# model.net
KiCad netlist of a schematic drawn in EAGLE
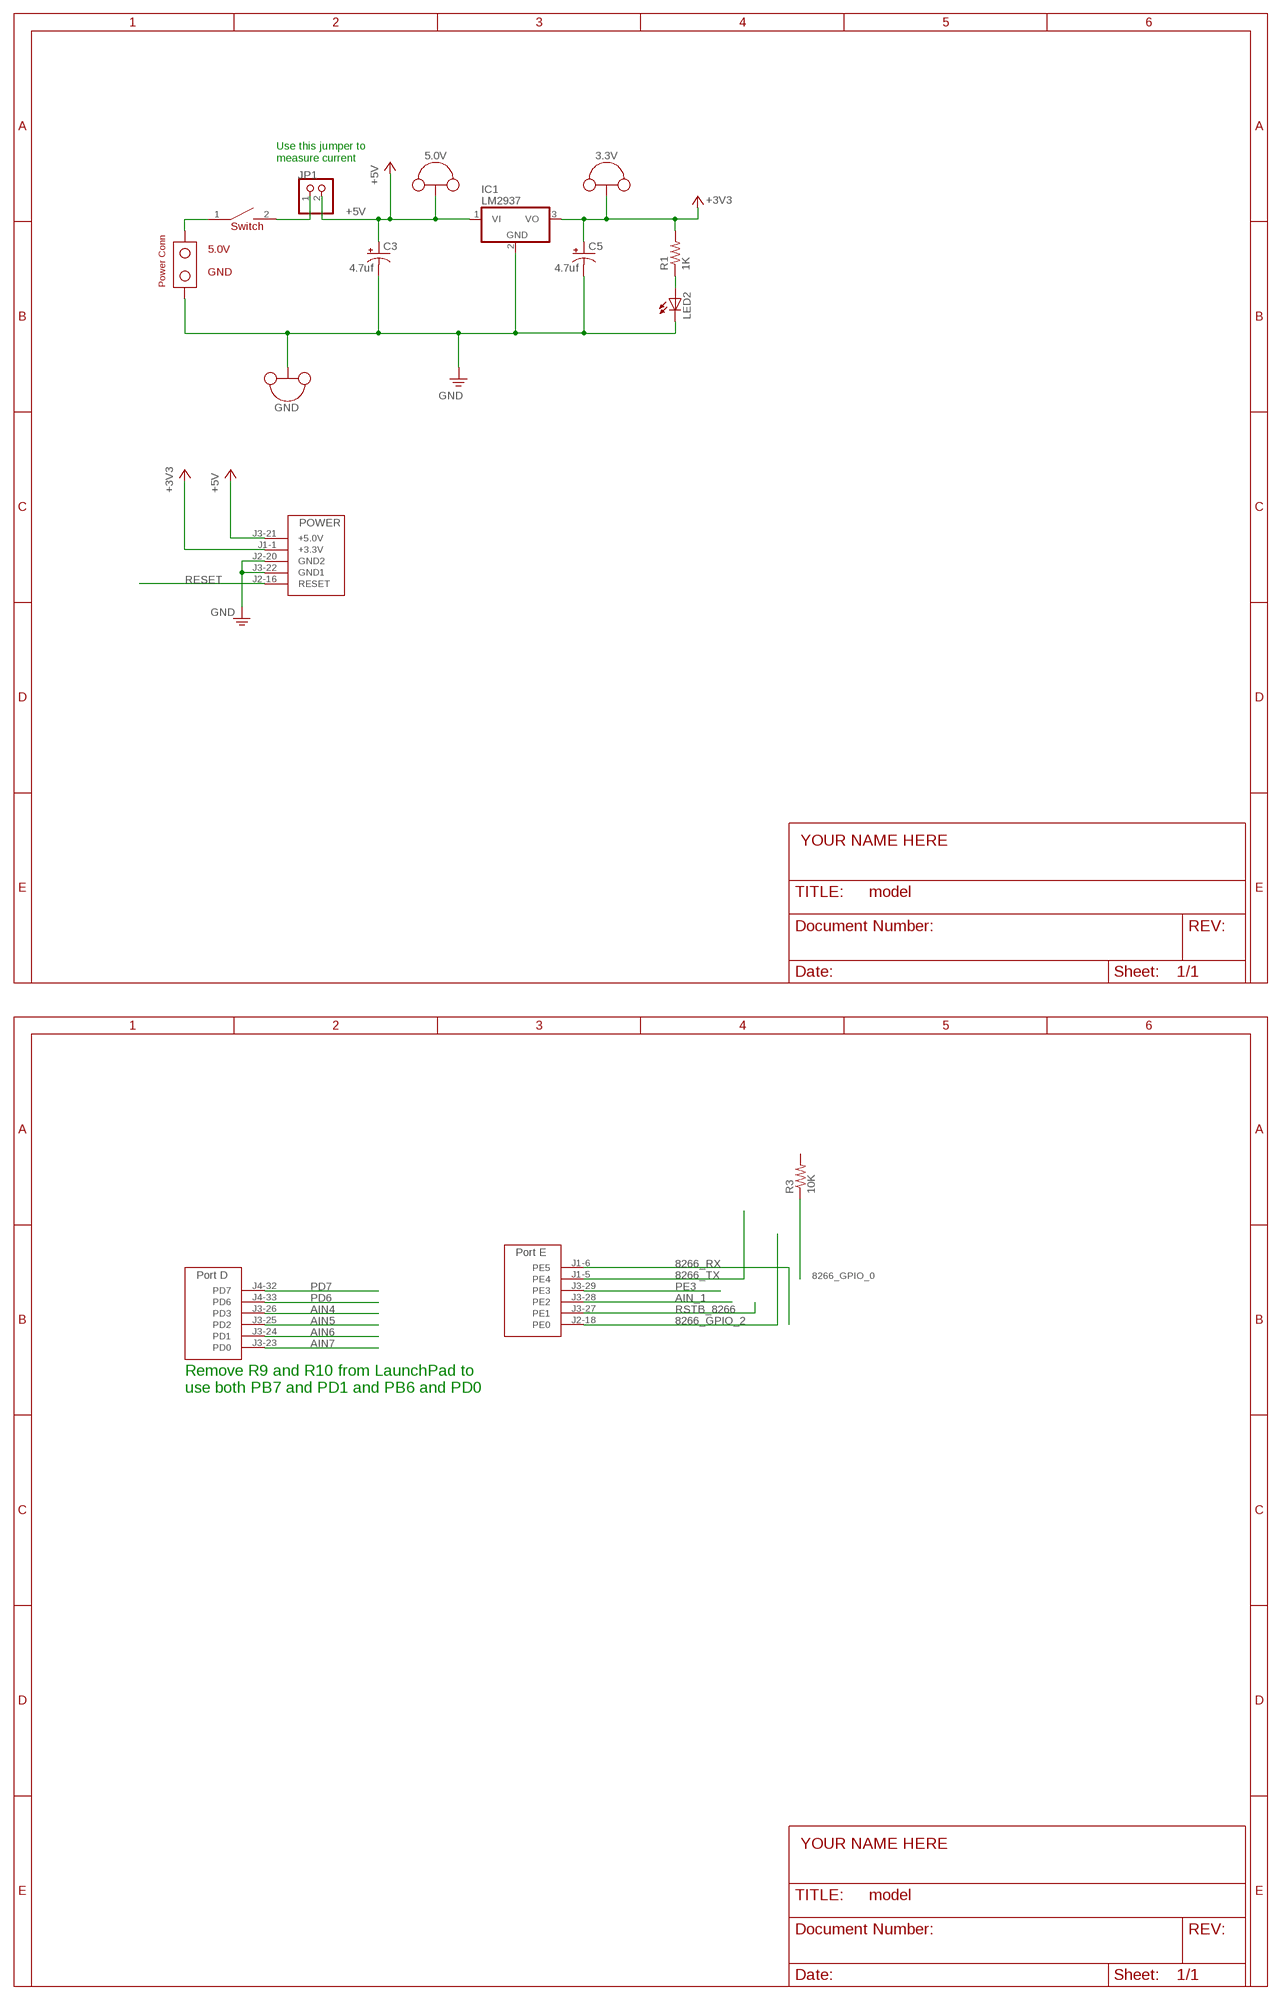
[diagram p0: schematic, sheet 1, part 1 of 2]
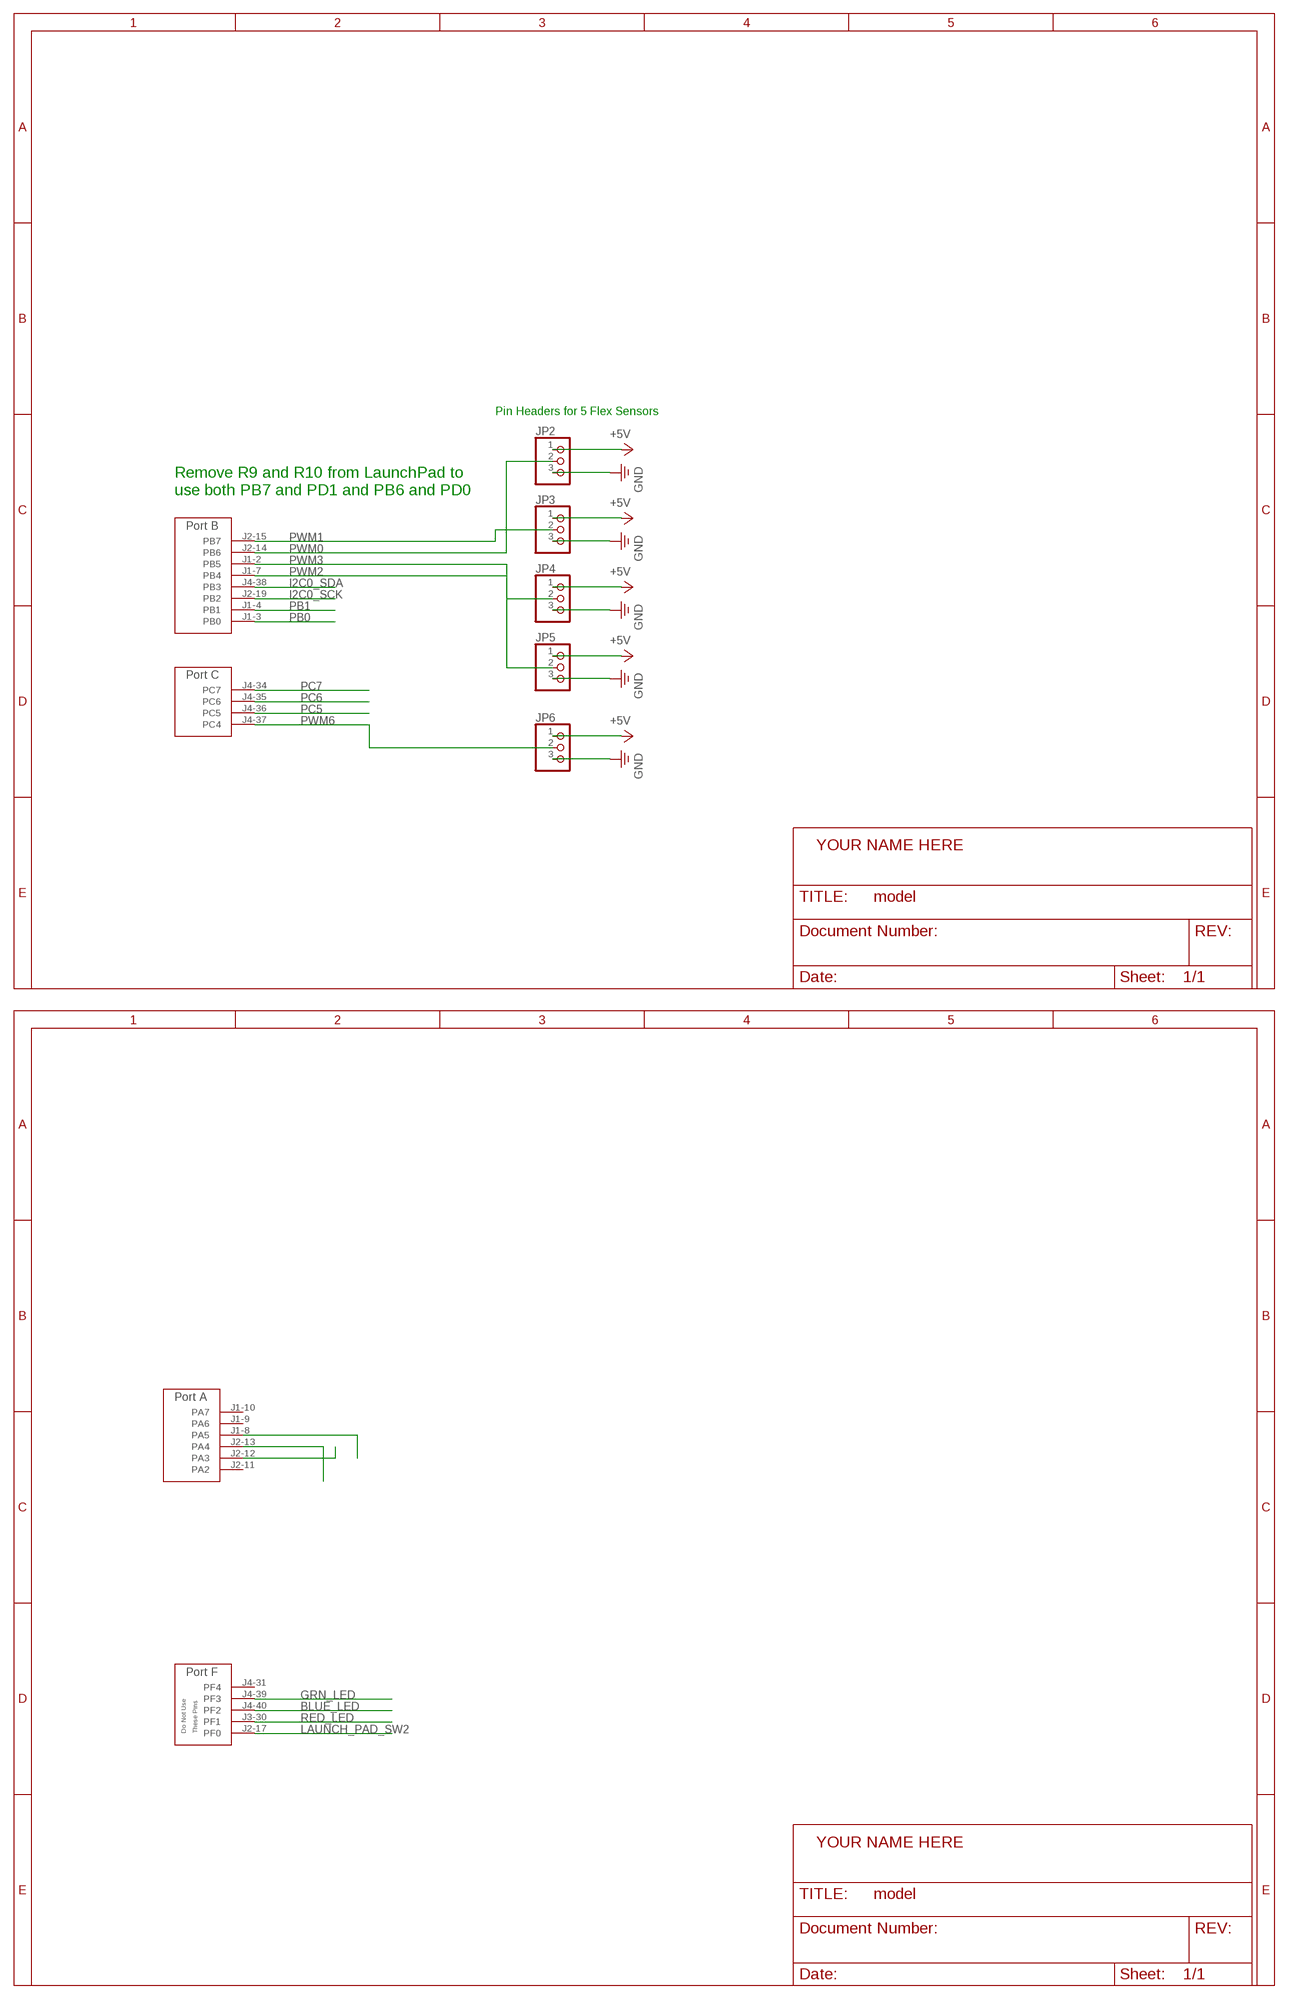
[diagram p1: schematic, sheet 1, part 2 of 2]

(export (version "E")
  (design (tool "Eeschema 10.0.6"))
  (components
    (comp (ref "3.3V")
      (value "TP_LOOP")
      (footprint "eagle-import:TP_LOOP")
      (libsource (lib "eagle-import") (part "TP_LOOP"))
    )
    (comp (ref "5.0V")
      (value "TP_LOOP")
      (footprint "eagle-import:TP_LOOP")
      (libsource (lib "eagle-import") (part "TP_LOOP"))
    )
    (comp (ref "C3")
      (value "4.7uf")
      (footprint "eagle-import:CAP200MILPOLARIZED")
      (libsource (lib "eagle-import") (part "CAPACITOR_POLARIZEDE5-6"))
    )
    (comp (ref "C5")
      (value "4.7uf")
      (footprint "eagle-import:CAP200MILPOLARIZED")
      (libsource (lib "eagle-import") (part "CAPACITOR_POLARIZEDE5-6"))
    )
    (comp (ref "GND")
      (value "TP_LOOP")
      (footprint "eagle-import:TP_LOOP")
      (libsource (lib "eagle-import") (part "TP_LOOP"))
    )
    (comp (ref "IC1")
      (value "LM2937")
      (footprint "eagle-import:TO220")
      (libsource (lib "eagle-import") (part "LM2937"))
    )
    (comp (ref "JP1")
      (value "PINHD-1X2")
      (footprint "eagle-import:1X02")
      (libsource (lib "eagle-import") (part "PINHD-1X2"))
    )
    (comp (ref "JP2")
      (value "PINHD-1X3")
      (footprint "eagle-import:1X03")
      (libsource (lib "eagle-import") (part "PINHD-1X3"))
    )
    (comp (ref "JP3")
      (value "PINHD-1X3")
      (footprint "eagle-import:1X03")
      (libsource (lib "eagle-import") (part "PINHD-1X3"))
    )
    (comp (ref "JP4")
      (value "PINHD-1X3")
      (footprint "eagle-import:1X03")
      (libsource (lib "eagle-import") (part "PINHD-1X3"))
    )
    (comp (ref "JP5")
      (value "PINHD-1X3")
      (footprint "eagle-import:1X03")
      (libsource (lib "eagle-import") (part "PINHD-1X3"))
    )
    (comp (ref "JP6")
      (value "PINHD-1X3")
      (footprint "eagle-import:1X03")
      (libsource (lib "eagle-import") (part "PINHD-1X3"))
    )
    (comp (ref "LED2")
      (value "LED3MM")
      (footprint "eagle-import:LED3MM")
      (libsource (lib "eagle-import") (part "LED3MM"))
    )
    (comp (ref "R1")
      (value "1K")
      (footprint "eagle-import:RES200MIL")
      (libsource (lib "eagle-import") (part "RESISTOR0204/5"))
    )
    (comp (ref "R3")
      (value "10K")
      (footprint "eagle-import:RES300MIL")
      (libsource (lib "eagle-import") (part "RESISTOR0204/7"))
    )
    (comp (ref "U$2")
      (value "TM4C_BP")
      (footprint "eagle-import:TM4C_BOOSTER_PACK")
      (libsource (lib "eagle-import") (part "TM4C_BP"))
    )
    (comp (ref "U$5")
      (value "POWER_CONN")
      (footprint "eagle-import:POWER_CONN")
      (libsource (lib "eagle-import") (part "POWER_CONN"))
    )
    (comp (ref "U$6")
      (value "SW_POWER_100MIL")
      (footprint "eagle-import:SW_POWER")
      (libsource (lib "eagle-import") (part "SW_POWER_100MIL"))
    )
  )
  (nets
    (net (code "1") (name "+3V3") (class "Default")
      (node (ref "3.3V") (pin "P$1") (pinfunction "TP_P$1") (pintype "bidirectional"))
      (node (ref "3.3V") (pin "P$2") (pinfunction "TP_P$2") (pintype "bidirectional"))
      (node (ref "C5") (pin "+") (pinfunction "+_+") (pintype "passive"))
      (node (ref "IC1") (pin "3") (pinfunction "VO_3") (pintype "passive"))
      (node (ref "R1") (pin "2") (pinfunction "2_2") (pintype "passive"))
      (node (ref "U$2") (pin "J1-1") (pinfunction "+3.3V_J1-1") (pintype "bidirectional"))
    )
    (net (code "2") (name "+5V") (class "Default")
      (node (ref "5.0V") (pin "P$1") (pinfunction "TP_P$1") (pintype "bidirectional"))
      (node (ref "5.0V") (pin "P$2") (pinfunction "TP_P$2") (pintype "bidirectional"))
      (node (ref "C3") (pin "+") (pinfunction "+_+") (pintype "passive"))
      (node (ref "IC1") (pin "1") (pinfunction "VI_1") (pintype "input"))
      (node (ref "JP1") (pin "2") (pinfunction "2_2") (pintype "passive"))
      (node (ref "JP2") (pin "1") (pinfunction "1_1") (pintype "passive"))
      (node (ref "JP3") (pin "1") (pinfunction "1_1") (pintype "passive"))
      (node (ref "JP4") (pin "1") (pinfunction "1_1") (pintype "passive"))
      (node (ref "JP5") (pin "1") (pinfunction "1_1") (pintype "passive"))
      (node (ref "JP6") (pin "1") (pinfunction "1_1") (pintype "passive"))
      (node (ref "U$2") (pin "J3-21") (pinfunction "+5.0V_J3-21") (pintype "bidirectional"))
    )
    (net (code "3") (name "/8266_GPIO_0") (class "Default")
      (node (ref "R3") (pin "1") (pinfunction "1_1") (pintype "passive"))
    )
    (net (code "4") (name "/8266_GPIO_2") (class "Default")
      (node (ref "U$2") (pin "J2-18") (pinfunction "PE0_J2-18") (pintype "bidirectional"))
    )
    (net (code "5") (name "/8266_RX") (class "Default")
      (node (ref "U$2") (pin "J1-6") (pinfunction "PE5_J1-6") (pintype "bidirectional"))
    )
    (net (code "6") (name "/8266_TX") (class "Default")
      (node (ref "U$2") (pin "J1-5") (pinfunction "PE4_J1-5") (pintype "bidirectional"))
    )
    (net (code "7") (name "/AIN4") (class "Default")
      (node (ref "U$2") (pin "J3-26") (pinfunction "PD3_J3-26") (pintype "bidirectional"))
    )
    (net (code "8") (name "/AIN5") (class "Default")
      (node (ref "U$2") (pin "J3-25") (pinfunction "PD2_J3-25") (pintype "bidirectional"))
    )
    (net (code "9") (name "/AIN6") (class "Default")
      (node (ref "U$2") (pin "J3-24") (pinfunction "PD1_J3-24") (pintype "bidirectional"))
    )
    (net (code "10") (name "/AIN7") (class "Default")
      (node (ref "U$2") (pin "J3-23") (pinfunction "PD0_J3-23") (pintype "bidirectional"))
    )
    (net (code "11") (name "/AIN_1") (class "Default")
      (node (ref "U$2") (pin "J3-28") (pinfunction "PE2_J3-28") (pintype "bidirectional"))
    )
    (net (code "12") (name "/BLUE_LED") (class "Default")
      (node (ref "U$2") (pin "J4-40") (pinfunction "PF2_J4-40") (pintype "bidirectional"))
    )
    (net (code "13") (name "/GRN_LED") (class "Default")
      (node (ref "U$2") (pin "J4-39") (pinfunction "PF3_J4-39") (pintype "bidirectional"))
    )
    (net (code "14") (name "/I2C0_SCK") (class "Default")
      (node (ref "U$2") (pin "J2-19") (pinfunction "PB2_J2-19") (pintype "bidirectional"))
    )
    (net (code "15") (name "/I2C0_SDA") (class "Default")
      (node (ref "U$2") (pin "J4-38") (pinfunction "PB3_J4-38") (pintype "bidirectional"))
    )
    (net (code "16") (name "/LAUNCH_PAD_SW2") (class "Default")
      (node (ref "U$2") (pin "J2-17") (pinfunction "PF0_J2-17") (pintype "bidirectional"))
    )
    (net (code "17") (name "/PB0") (class "Default")
      (node (ref "U$2") (pin "J1-3") (pinfunction "PB0_J1-3") (pintype "bidirectional"))
    )
    (net (code "18") (name "/PB1") (class "Default")
      (node (ref "U$2") (pin "J1-4") (pinfunction "PB1_J1-4") (pintype "bidirectional"))
    )
    (net (code "19") (name "/PC5") (class "Default")
      (node (ref "U$2") (pin "J4-36") (pinfunction "PC5_J4-36") (pintype "bidirectional"))
    )
    (net (code "20") (name "/PC6") (class "Default")
      (node (ref "U$2") (pin "J4-35") (pinfunction "PC6_J4-35") (pintype "bidirectional"))
    )
    (net (code "21") (name "/PC7") (class "Default")
      (node (ref "U$2") (pin "J4-34") (pinfunction "PC7_J4-34") (pintype "bidirectional"))
    )
    (net (code "22") (name "/PD6") (class "Default")
      (node (ref "U$2") (pin "J4-33") (pinfunction "PD6_J4-33") (pintype "bidirectional"))
    )
    (net (code "23") (name "/PD7") (class "Default")
      (node (ref "U$2") (pin "J4-32") (pinfunction "PD7_J4-32") (pintype "bidirectional"))
    )
    (net (code "24") (name "/PE3") (class "Default")
      (node (ref "U$2") (pin "J3-29") (pinfunction "PE3_J3-29") (pintype "bidirectional"))
    )
    (net (code "25") (name "/PWM0") (class "Default")
      (node (ref "JP2") (pin "2") (pinfunction "2_2") (pintype "passive"))
      (node (ref "U$2") (pin "J2-14") (pinfunction "PB6_J2-14") (pintype "bidirectional"))
    )
    (net (code "26") (name "/PWM1") (class "Default")
      (node (ref "JP3") (pin "2") (pinfunction "2_2") (pintype "passive"))
      (node (ref "U$2") (pin "J2-15") (pinfunction "PB7_J2-15") (pintype "bidirectional"))
    )
    (net (code "27") (name "/PWM2") (class "Default")
      (node (ref "JP4") (pin "2") (pinfunction "2_2") (pintype "passive"))
      (node (ref "U$2") (pin "J1-7") (pinfunction "PB4_J1-7") (pintype "bidirectional"))
    )
    (net (code "28") (name "/PWM3") (class "Default")
      (node (ref "JP5") (pin "2") (pinfunction "2_2") (pintype "passive"))
      (node (ref "U$2") (pin "J1-2") (pinfunction "PB5_J1-2") (pintype "bidirectional"))
    )
    (net (code "29") (name "/PWM6") (class "Default")
      (node (ref "JP6") (pin "2") (pinfunction "2_2") (pintype "passive"))
      (node (ref "U$2") (pin "J4-37") (pinfunction "PC4_J4-37") (pintype "bidirectional"))
    )
    (net (code "30") (name "/RED_LED") (class "Default")
      (node (ref "U$2") (pin "J3-30") (pinfunction "PF1_J3-30") (pintype "bidirectional"))
    )
    (net (code "31") (name "/RESET") (class "Default")
      (node (ref "U$2") (pin "J2-16") (pinfunction "RESET_J2-16") (pintype "bidirectional"))
    )
    (net (code "32") (name "/RSTB_8266") (class "Default")
      (node (ref "U$2") (pin "J3-27") (pinfunction "PE1_J3-27") (pintype "bidirectional"))
    )
    (net (code "33") (name "GND") (class "Default")
      (node (ref "C3") (pin "-") (pinfunction "-_-") (pintype "passive"))
      (node (ref "C5") (pin "-") (pinfunction "-_-") (pintype "passive"))
      (node (ref "GND") (pin "P$1") (pinfunction "TP_P$1") (pintype "bidirectional"))
      (node (ref "GND") (pin "P$2") (pinfunction "TP_P$2") (pintype "bidirectional"))
      (node (ref "IC1") (pin "2") (pinfunction "GND_2") (pintype "passive"))
      (node (ref "JP2") (pin "3") (pinfunction "3_3") (pintype "passive"))
      (node (ref "JP3") (pin "3") (pinfunction "3_3") (pintype "passive"))
      (node (ref "JP4") (pin "3") (pinfunction "3_3") (pintype "passive"))
      (node (ref "JP5") (pin "3") (pinfunction "3_3") (pintype "passive"))
      (node (ref "JP6") (pin "3") (pinfunction "3_3") (pintype "passive"))
      (node (ref "LED2") (pin "K") (pinfunction "C_K") (pintype "passive"))
      (node (ref "U$2") (pin "J2-20") (pinfunction "GND2_J2-20") (pintype "bidirectional"))
      (node (ref "U$2") (pin "J3-22") (pinfunction "GND1_J3-22") (pintype "bidirectional"))
      (node (ref "U$5") (pin "GND") (pinfunction "GND_GND") (pintype "bidirectional"))
    )
    (net (code "34") (name "Net-(LED2-PadA)") (class "Default")
      (node (ref "LED2") (pin "A") (pinfunction "A_A") (pintype "passive"))
      (node (ref "R1") (pin "1") (pinfunction "1_1") (pintype "passive"))
    )
    (net (code "35") (name "Net-(U$6-P$1)") (class "Default")
      (node (ref "U$5") (pin "VDD") (pinfunction "VDD_VDD") (pintype "bidirectional"))
      (node (ref "U$6") (pin "1") (pinfunction "P$1_1") (pintype "bidirectional"))
    )
    (net (code "36") (name "Net-(U$6-P$2)") (class "Default")
      (node (ref "JP1") (pin "1") (pinfunction "1_1") (pintype "passive"))
      (node (ref "U$6") (pin "2") (pinfunction "P$2_2") (pintype "bidirectional"))
    )
    (net (code "37") (name "unconnected-(R3-Pad2)") (class "Default")
      (node (ref "R3") (pin "2") (pinfunction "2_2") (pintype "passive"))
    )
    (net (code "38") (name "unconnected-(U$2A-PA2-PadJ2-11)") (class "Default")
      (node (ref "U$2") (pin "J2-11") (pinfunction "PA2_J2-11") (pintype "bidirectional"))
    )
    (net (code "39") (name "unconnected-(U$2A-PA3-PadJ2-12)") (class "Default")
      (node (ref "U$2") (pin "J2-12") (pinfunction "PA3_J2-12") (pintype "bidirectional"))
    )
    (net (code "40") (name "unconnected-(U$2A-PA4-PadJ2-13)") (class "Default")
      (node (ref "U$2") (pin "J2-13") (pinfunction "PA4_J2-13") (pintype "bidirectional"))
    )
    (net (code "41") (name "unconnected-(U$2A-PA5-PadJ1-8)") (class "Default")
      (node (ref "U$2") (pin "J1-8") (pinfunction "PA5_J1-8") (pintype "bidirectional"))
    )
    (net (code "42") (name "unconnected-(U$2A-PA6-PadJ1-9)") (class "Default")
      (node (ref "U$2") (pin "J1-9") (pinfunction "PA6_J1-9") (pintype "bidirectional"))
    )
    (net (code "43") (name "unconnected-(U$2A-PA7-PadJ1-10)") (class "Default")
      (node (ref "U$2") (pin "J1-10") (pinfunction "PA7_J1-10") (pintype "bidirectional"))
    )
    (net (code "44") (name "unconnected-(U$2F-PF4-PadJ4-31)") (class "Default")
      (node (ref "U$2") (pin "J4-31") (pinfunction "PF4_J4-31") (pintype "bidirectional"))
    )
  )
)
